# oresat-batteries-prototype.net
KiCad netlist of a schematic drawn in EAGLE
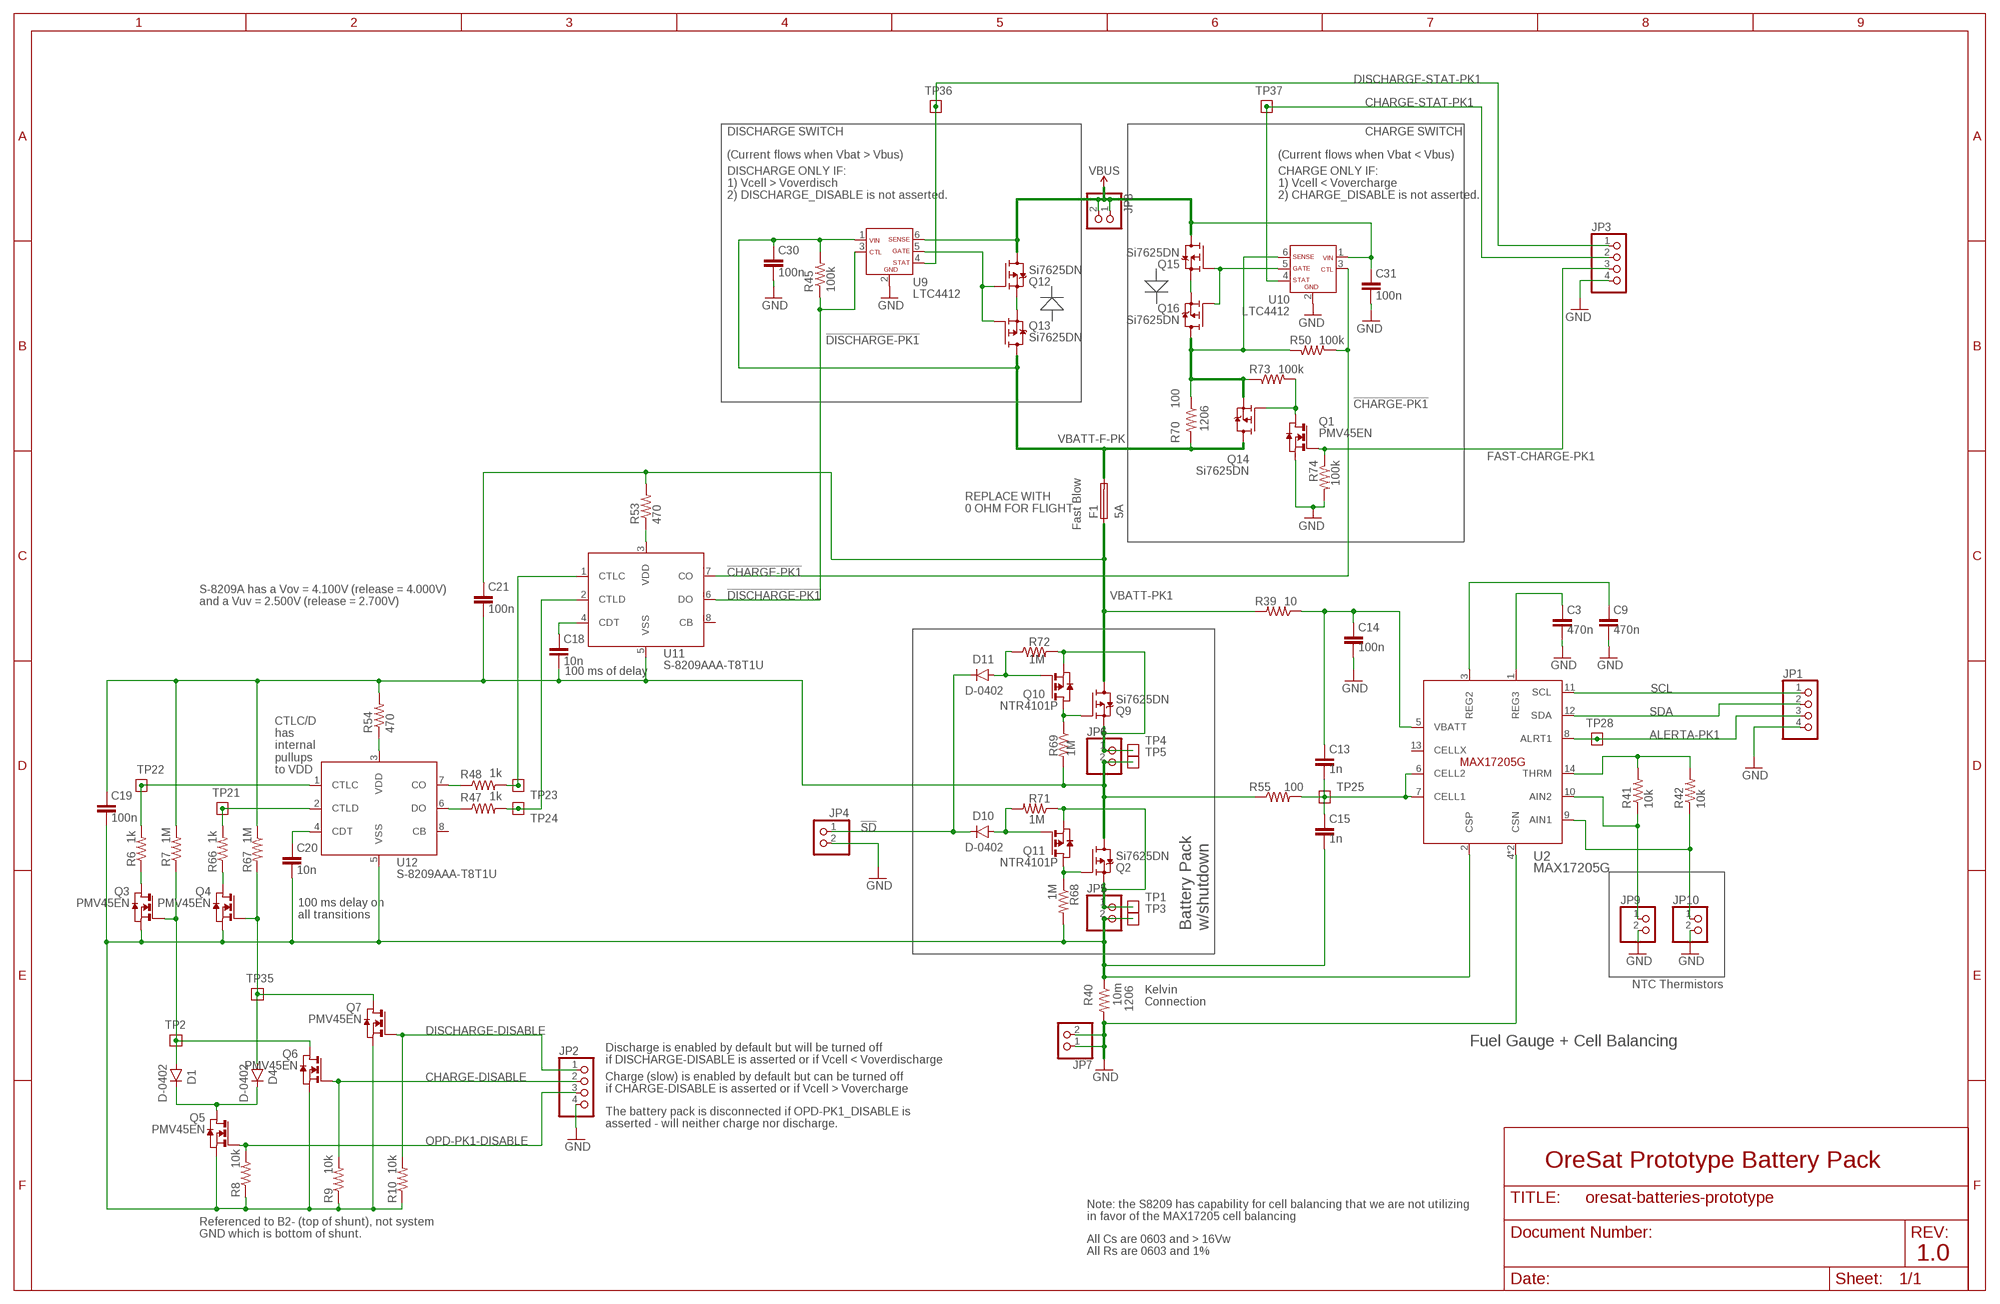
[diagram p0: schematic, sheet 1]

(export (version "E")
  (design (tool "Eeschema 10.0.6"))
  (components
    (comp (ref "C3")
      (value "470n")
      (footprint "eagle-import:.0603-C-NOSILK")
      (libsource (lib "eagle-import") (part "C-EU0603-C-NOSILK"))
    )
    (comp (ref "C9")
      (value "470n")
      (footprint "eagle-import:.0603-C-NOSILK")
      (libsource (lib "eagle-import") (part "C-EU0603-C-NOSILK"))
    )
    (comp (ref "C13")
      (value "1n")
      (footprint "eagle-import:.0603-C-NOSILK")
      (libsource (lib "eagle-import") (part "C-EU0603-C-NOSILK"))
    )
    (comp (ref "C14")
      (value "100n")
      (footprint "eagle-import:.0603-C-NOSILK")
      (libsource (lib "eagle-import") (part "C-EU0603-C-NOSILK"))
    )
    (comp (ref "C15")
      (value "1n")
      (footprint "eagle-import:.0603-C-NOSILK")
      (libsource (lib "eagle-import") (part "C-EU0603-C-NOSILK"))
    )
    (comp (ref "C18")
      (value "10n")
      (footprint "eagle-import:.0603-C-NOSILK")
      (libsource (lib "eagle-import") (part "C-EU0603-C-NOSILK"))
    )
    (comp (ref "C19")
      (value "100n")
      (footprint "eagle-import:.0603-C-NOSILK")
      (libsource (lib "eagle-import") (part "C-EU0603-C-NOSILK"))
    )
    (comp (ref "C20")
      (value "10n")
      (footprint "eagle-import:.0603-C-NOSILK")
      (libsource (lib "eagle-import") (part "C-EU0603-C-NOSILK"))
    )
    (comp (ref "C21")
      (value "100n")
      (footprint "eagle-import:.0603-C-NOSILK")
      (libsource (lib "eagle-import") (part "C-EU0603-C-NOSILK"))
    )
    (comp (ref "C30")
      (value "100n")
      (footprint "eagle-import:.0603-C-NOSILK")
      (libsource (lib "eagle-import") (part "C-EU0603-C-NOSILK"))
    )
    (comp (ref "C31")
      (value "100n")
      (footprint "eagle-import:.0603-C-NOSILK")
      (libsource (lib "eagle-import") (part "C-EU0603-C-NOSILK"))
    )
    (comp (ref "D1")
      (value "D-0402")
      (footprint "eagle-import:.0402-B-NOSILK-DIODE")
      (fields (field (name "MFR") "Micro Commercial Co") (field (name "MPN") "1N4148WL2-TP"))
      (libsource (lib "eagle-import") (part "D-0402"))
    )
    (comp (ref "D4")
      (value "D-0402")
      (footprint "eagle-import:.0402-B-NOSILK-DIODE")
      (fields (field (name "MFR") "Micro Commercial Co") (field (name "MPN") "1N4148WL2-TP"))
      (libsource (lib "eagle-import") (part "D-0402"))
    )
    (comp (ref "D10")
      (value "D-0402")
      (footprint "eagle-import:.0402-B-NOSILK-DIODE")
      (fields (field (name "MFR") "Micro Commercial Co") (field (name "MPN") "1N4148WL2-TP"))
      (libsource (lib "eagle-import") (part "D-0402"))
    )
    (comp (ref "D11")
      (value "D-0402")
      (footprint "eagle-import:.0402-B-NOSILK-DIODE")
      (fields (field (name "MFR") "Micro Commercial Co") (field (name "MPN") "1N4148WL2-TP"))
      (libsource (lib "eagle-import") (part "D-0402"))
    )
    (comp (ref "F1")
      (value "5A")
      (footprint "eagle-import:C0603")
      (fields (field (name "MFR") "Panasonic") (field (name "MPN") "ERB-RE5R00V"))
      (libsource (lib "eagle-import") (part "F-ERB_RE5R00V-FUSE"))
    )
    (comp (ref "JP1")
      (value "PINHD-1X4")
      (footprint "eagle-import:1X04")
      (libsource (lib "eagle-import") (part "PINHD-1X4"))
    )
    (comp (ref "JP2")
      (value "PINHD-1X4")
      (footprint "eagle-import:1X04")
      (libsource (lib "eagle-import") (part "PINHD-1X4"))
    )
    (comp (ref "JP3")
      (value "PINHD-1X4")
      (footprint "eagle-import:1X04")
      (libsource (lib "eagle-import") (part "PINHD-1X4"))
    )
    (comp (ref "JP4")
      (value "PINHD-1X2")
      (footprint "eagle-import:1X02")
      (libsource (lib "eagle-import") (part "PINHD-1X2"))
    )
    (comp (ref "JP5")
      (value "PINHD-1X2")
      (footprint "eagle-import:1X02")
      (libsource (lib "eagle-import") (part "PINHD-1X2"))
    )
    (comp (ref "JP6")
      (value "PINHD-1X2")
      (footprint "eagle-import:1X02")
      (libsource (lib "eagle-import") (part "PINHD-1X2"))
    )
    (comp (ref "JP7")
      (value "PINHD-1X2")
      (footprint "eagle-import:1X02")
      (libsource (lib "eagle-import") (part "PINHD-1X2"))
    )
    (comp (ref "JP8")
      (value "PINHD-1X2")
      (footprint "eagle-import:1X02")
      (libsource (lib "eagle-import") (part "PINHD-1X2"))
    )
    (comp (ref "JP9")
      (value "PINHD-1X2")
      (footprint "eagle-import:1X02")
      (libsource (lib "eagle-import") (part "PINHD-1X2"))
    )
    (comp (ref "JP10")
      (value "PINHD-1X2")
      (footprint "eagle-import:1X02")
      (libsource (lib "eagle-import") (part "PINHD-1X2"))
    )
    (comp (ref "Q1")
      (value "PMV45EN")
      (footprint "eagle-import:SOT23")
      (fields (field (name "MFR") "Diodes Inc") (field (name "MPN") "DMG2302UK-7"))
      (libsource (lib "eagle-import") (part "PMV45EN"))
    )
    (comp (ref "Q2")
      (value "Si7625DN")
      (footprint "eagle-import:POWERPAK-1212-8")
      (fields (field (name "MFR") "Vishay Siliconix") (field (name "MPN") "SI7625DN-T1-GE3"))
      (libsource (lib "eagle-import") (part "Q-VISHAY-MOSFET-PCH-POWERPAK-1212-8"))
    )
    (comp (ref "Q3")
      (value "PMV45EN")
      (footprint "eagle-import:SOT23")
      (fields (field (name "MFR") "Diodes Inc") (field (name "MPN") "DMG2302UK-7"))
      (libsource (lib "eagle-import") (part "PMV45EN"))
    )
    (comp (ref "Q4")
      (value "PMV45EN")
      (footprint "eagle-import:SOT23")
      (fields (field (name "MFR") "Diodes Inc") (field (name "MPN") "DMG2302UK-7"))
      (libsource (lib "eagle-import") (part "PMV45EN"))
    )
    (comp (ref "Q5")
      (value "PMV45EN")
      (footprint "eagle-import:SOT23")
      (fields (field (name "MFR") "Diodes Inc") (field (name "MPN") "DMG2302UK-7"))
      (libsource (lib "eagle-import") (part "PMV45EN"))
    )
    (comp (ref "Q6")
      (value "PMV45EN")
      (footprint "eagle-import:SOT23")
      (fields (field (name "MFR") "Diodes Inc") (field (name "MPN") "DMG2302UK-7"))
      (libsource (lib "eagle-import") (part "PMV45EN"))
    )
    (comp (ref "Q7")
      (value "PMV45EN")
      (footprint "eagle-import:SOT23")
      (fields (field (name "MFR") "Diodes Inc") (field (name "MPN") "DMG2302UK-7"))
      (libsource (lib "eagle-import") (part "PMV45EN"))
    )
    (comp (ref "Q9")
      (value "Si7625DN")
      (footprint "eagle-import:POWERPAK-1212-8")
      (fields (field (name "MFR") "Vishay Siliconix") (field (name "MPN") "SI7625DN-T1-GE3"))
      (libsource (lib "eagle-import") (part "Q-VISHAY-MOSFET-PCH-POWERPAK-1212-8"))
    )
    (comp (ref "Q10")
      (value "NTR4101P")
      (footprint "eagle-import:SOT23")
      (fields (field (name "MFR") "Diodes Inc") (field (name "MPN") "DMG3401LSN-7"))
      (libsource (lib "eagle-import") (part "NTR4101P"))
    )
    (comp (ref "Q11")
      (value "NTR4101P")
      (footprint "eagle-import:SOT23")
      (fields (field (name "MFR") "Diodes Inc") (field (name "MPN") "DMG3401LSN-7"))
      (libsource (lib "eagle-import") (part "NTR4101P"))
    )
    (comp (ref "Q12")
      (value "Si7625DN")
      (footprint "eagle-import:POWERPAK-1212-8")
      (fields (field (name "MFR") "Vishay Siliconix") (field (name "MPN") "SI7625DN-T1-GE3"))
      (libsource (lib "eagle-import") (part "Q-VISHAY-MOSFET-PCH-POWERPAK-1212-8"))
    )
    (comp (ref "Q13")
      (value "Si7625DN")
      (footprint "eagle-import:POWERPAK-1212-8")
      (fields (field (name "MFR") "Vishay Siliconix") (field (name "MPN") "SI7625DN-T1-GE3"))
      (libsource (lib "eagle-import") (part "Q-VISHAY-MOSFET-PCH-POWERPAK-1212-8"))
    )
    (comp (ref "Q14")
      (value "Si7625DN")
      (footprint "eagle-import:POWERPAK-1212-8")
      (fields (field (name "MFR") "Vishay Siliconix") (field (name "MPN") "SI7625DN-T1-GE3"))
      (libsource (lib "eagle-import") (part "Q-VISHAY-MOSFET-PCH-POWERPAK-1212-8"))
    )
    (comp (ref "Q15")
      (value "Si7625DN")
      (footprint "eagle-import:POWERPAK-1212-8")
      (fields (field (name "MFR") "Vishay Siliconix") (field (name "MPN") "SI7625DN-T1-GE3"))
      (libsource (lib "eagle-import") (part "Q-VISHAY-MOSFET-PCH-POWERPAK-1212-8"))
    )
    (comp (ref "Q16")
      (value "Si7625DN")
      (footprint "eagle-import:POWERPAK-1212-8")
      (fields (field (name "MFR") "Vishay Siliconix") (field (name "MPN") "SI7625DN-T1-GE3"))
      (libsource (lib "eagle-import") (part "Q-VISHAY-MOSFET-PCH-POWERPAK-1212-8"))
    )
    (comp (ref "R6")
      (value "1k")
      (footprint "eagle-import:.0603-C-NOSILK")
      (libsource (lib "eagle-import") (part "R-US_0603-C-NOSILK"))
    )
    (comp (ref "R7")
      (value "1M")
      (footprint "eagle-import:.0603-C-NOSILK")
      (libsource (lib "eagle-import") (part "R-US_0603-C-NOSILK"))
    )
    (comp (ref "R8")
      (value "10k")
      (footprint "eagle-import:.0603-C-NOSILK")
      (libsource (lib "eagle-import") (part "R-US_0603-C-NOSILK"))
    )
    (comp (ref "R9")
      (value "10k")
      (footprint "eagle-import:.0603-C-NOSILK")
      (libsource (lib "eagle-import") (part "R-US_0603-C-NOSILK"))
    )
    (comp (ref "R10")
      (value "10k")
      (footprint "eagle-import:.0603-C-NOSILK")
      (libsource (lib "eagle-import") (part "R-US_0603-C-NOSILK"))
    )
    (comp (ref "R39")
      (value "10")
      (footprint "eagle-import:.0603-C-NOSILK")
      (libsource (lib "eagle-import") (part "R-US_0603-C-NOSILK"))
    )
    (comp (ref "R40")
      (value "10m")
      (footprint "eagle-import:1206-C")
      (libsource (lib "eagle-import") (part "R-US_1206-C"))
    )
    (comp (ref "R41")
      (value "10k")
      (footprint "eagle-import:.0603-C-NOSILK")
      (libsource (lib "eagle-import") (part "R-US_0603-C-NOSILK"))
    )
    (comp (ref "R42")
      (value "10k")
      (footprint "eagle-import:.0603-C-NOSILK")
      (libsource (lib "eagle-import") (part "R-US_0603-C-NOSILK"))
    )
    (comp (ref "R45")
      (value "100k")
      (footprint "eagle-import:.0603-C-NOSILK")
      (libsource (lib "eagle-import") (part "R-US_0603-C-NOSILK"))
    )
    (comp (ref "R47")
      (value "1k")
      (footprint "eagle-import:.0603-C-NOSILK")
      (libsource (lib "eagle-import") (part "R-US_0603-C-NOSILK"))
    )
    (comp (ref "R48")
      (value "1k")
      (footprint "eagle-import:.0603-C-NOSILK")
      (libsource (lib "eagle-import") (part "R-US_0603-C-NOSILK"))
    )
    (comp (ref "R50")
      (value "100k")
      (footprint "eagle-import:.0603-C-NOSILK")
      (libsource (lib "eagle-import") (part "R-US_0603-C-NOSILK"))
    )
    (comp (ref "R53")
      (value "470")
      (footprint "eagle-import:.0603-C-NOSILK")
      (libsource (lib "eagle-import") (part "R-US_0603-C-NOSILK"))
    )
    (comp (ref "R54")
      (value "470")
      (footprint "eagle-import:.0603-C-NOSILK")
      (libsource (lib "eagle-import") (part "R-US_0603-C-NOSILK"))
    )
    (comp (ref "R55")
      (value "100")
      (footprint "eagle-import:.0603-C-NOSILK")
      (libsource (lib "eagle-import") (part "R-US_0603-C-NOSILK"))
    )
    (comp (ref "R66")
      (value "1k")
      (footprint "eagle-import:.0603-C-NOSILK")
      (libsource (lib "eagle-import") (part "R-US_0603-C-NOSILK"))
    )
    (comp (ref "R67")
      (value "1M")
      (footprint "eagle-import:.0603-C-NOSILK")
      (libsource (lib "eagle-import") (part "R-US_0603-C-NOSILK"))
    )
    (comp (ref "R68")
      (value "1M")
      (footprint "eagle-import:.0603-C-NOSILK")
      (libsource (lib "eagle-import") (part "R-US_0603-C-NOSILK"))
    )
    (comp (ref "R69")
      (value "1M")
      (footprint "eagle-import:.0603-C-NOSILK")
      (libsource (lib "eagle-import") (part "R-US_0603-C-NOSILK"))
    )
    (comp (ref "R70")
      (value "100")
      (footprint "eagle-import:1206-C")
      (libsource (lib "eagle-import") (part "R-US_1206-C"))
    )
    (comp (ref "R71")
      (value "1M")
      (footprint "eagle-import:.0603-C-NOSILK")
      (libsource (lib "eagle-import") (part "R-US_0603-C-NOSILK"))
    )
    (comp (ref "R72")
      (value "1M")
      (footprint "eagle-import:.0603-C-NOSILK")
      (libsource (lib "eagle-import") (part "R-US_0603-C-NOSILK"))
    )
    (comp (ref "R73")
      (value "100k")
      (footprint "eagle-import:.0603-C-NOSILK")
      (libsource (lib "eagle-import") (part "R-US_0603-C-NOSILK"))
    )
    (comp (ref "R74")
      (value "100k")
      (footprint "eagle-import:.0603-C-NOSILK")
      (libsource (lib "eagle-import") (part "R-US_0603-C-NOSILK"))
    )
    (comp (ref "TP1")
      (value "TEST-POINT")
      (footprint "eagle-import:2MM-TEST-POINT")
      (libsource (lib "eagle-import") (part "TEST-POINT"))
    )
    (comp (ref "TP2")
      (value "TEST-POINT")
      (footprint "eagle-import:2MM-TEST-POINT")
      (libsource (lib "eagle-import") (part "TEST-POINT"))
    )
    (comp (ref "TP3")
      (value "TEST-POINT")
      (footprint "eagle-import:2MM-TEST-POINT")
      (libsource (lib "eagle-import") (part "TEST-POINT"))
    )
    (comp (ref "TP4")
      (value "TEST-POINT")
      (footprint "eagle-import:2MM-TEST-POINT")
      (libsource (lib "eagle-import") (part "TEST-POINT"))
    )
    (comp (ref "TP5")
      (value "TEST-POINT")
      (footprint "eagle-import:2MM-TEST-POINT")
      (libsource (lib "eagle-import") (part "TEST-POINT"))
    )
    (comp (ref "TP21")
      (value "TEST-POINT")
      (footprint "eagle-import:2MM-TEST-POINT")
      (libsource (lib "eagle-import") (part "TEST-POINT"))
    )
    (comp (ref "TP22")
      (value "TEST-POINT")
      (footprint "eagle-import:2MM-TEST-POINT")
      (libsource (lib "eagle-import") (part "TEST-POINT"))
    )
    (comp (ref "TP23")
      (value "TEST-POINT")
      (footprint "eagle-import:2MM-TEST-POINT")
      (libsource (lib "eagle-import") (part "TEST-POINT"))
    )
    (comp (ref "TP24")
      (value "TEST-POINT")
      (footprint "eagle-import:2MM-TEST-POINT")
      (libsource (lib "eagle-import") (part "TEST-POINT"))
    )
    (comp (ref "TP25")
      (value "TEST-POINT")
      (footprint "eagle-import:2MM-TEST-POINT")
      (libsource (lib "eagle-import") (part "TEST-POINT"))
    )
    (comp (ref "TP28")
      (value "TEST-POINT")
      (footprint "eagle-import:2MM-TEST-POINT")
      (libsource (lib "eagle-import") (part "TEST-POINT"))
    )
    (comp (ref "TP35")
      (value "TEST-POINT")
      (footprint "eagle-import:2MM-TEST-POINT")
      (libsource (lib "eagle-import") (part "TEST-POINT"))
    )
    (comp (ref "TP36")
      (value "TEST-POINT")
      (footprint "eagle-import:2MM-TEST-POINT")
      (libsource (lib "eagle-import") (part "TEST-POINT"))
    )
    (comp (ref "TP37")
      (value "TEST-POINT")
      (footprint "eagle-import:2MM-TEST-POINT")
      (libsource (lib "eagle-import") (part "TEST-POINT"))
    )
    (comp (ref "U2")
      (value "MAX17205G")
      (footprint "eagle-import:21-0137I_T1433-2")
      (fields (field (name "MFR") "Maxim Integrated") (field (name "MPN") "MAX17205G+T"))
      (libsource (lib "eagle-import") (part "MAX17205G"))
    )
    (comp (ref "U9")
      (value "LTC4412")
      (footprint "eagle-import:SOT23-6")
      (fields (field (name "MFR") "Linear Technology") (field (name "MPN") "LTC4412HS6#TRMPBF"))
      (libsource (lib "eagle-import") (part "LTC4412"))
    )
    (comp (ref "U10")
      (value "LTC4412")
      (footprint "eagle-import:SOT23-6")
      (fields (field (name "MFR") "Linear Technology") (field (name "MPN") "LTC4412HS6#TRMPBF"))
      (libsource (lib "eagle-import") (part "LTC4412"))
    )
    (comp (ref "U11")
      (value "S-8209AAA-T8T1U")
      (footprint "eagle-import:TSSOP8")
      (fields (field (name "MFR") "Ablic"))
      (libsource (lib "eagle-import") (part "S-8209AXXT"))
    )
    (comp (ref "U12")
      (value "S-8209AAA-T8T1U")
      (footprint "eagle-import:TSSOP8")
      (fields (field (name "MFR") "Ablic"))
      (libsource (lib "eagle-import") (part "S-8209AXXT"))
    )
  )
  (nets
    (net (code "1") (name "/ALERTA-PK1") (class "Default")
      (node (ref "JP1") (pin "3") (pinfunction "3_3") (pintype "passive"))
      (node (ref "TP28") (pin "1") (pinfunction "1_1") (pintype "passive"))
      (node (ref "U2") (pin "8") (pinfunction "ALRT1_8") (pintype "output"))
    )
    (net (code "2") (name "/CHARGE-DISABLE") (class "Default")
      (node (ref "JP2") (pin "2") (pinfunction "2_2") (pintype "passive"))
      (node (ref "Q6") (pin "1") (pinfunction "G_1") (pintype "passive"))
      (node (ref "R9") (pin "2") (pinfunction "2_2") (pintype "passive"))
    )
    (net (code "3") (name "/CHARGE-STAT-PK1") (class "Default")
      (node (ref "JP3") (pin "2") (pinfunction "2_2") (pintype "passive"))
      (node (ref "TP37") (pin "1") (pinfunction "1_1") (pintype "passive"))
      (node (ref "U10") (pin "4") (pinfunction "STAT_4") (pintype "open_collector"))
    )
    (net (code "4") (name "/DISCHARGE-DISABLE") (class "Default")
      (node (ref "JP2") (pin "1") (pinfunction "1_1") (pintype "passive"))
      (node (ref "Q7") (pin "1") (pinfunction "G_1") (pintype "passive"))
      (node (ref "R10") (pin "2") (pinfunction "2_2") (pintype "passive"))
    )
    (net (code "5") (name "/DISCHARGE-STAT-PK1") (class "Default")
      (node (ref "JP3") (pin "1") (pinfunction "1_1") (pintype "passive"))
      (node (ref "TP36") (pin "1") (pinfunction "1_1") (pintype "passive"))
      (node (ref "U9") (pin "4") (pinfunction "STAT_4") (pintype "open_collector"))
    )
    (net (code "6") (name "/FAST-CHARGE-PK1") (class "Default")
      (node (ref "JP3") (pin "3") (pinfunction "3_3") (pintype "passive"))
      (node (ref "Q1") (pin "1") (pinfunction "G_1") (pintype "passive"))
      (node (ref "R74") (pin "1") (pinfunction "1_1") (pintype "passive"))
    )
    (net (code "7") (name "/OPD-PK1-DISABLE") (class "Default")
      (node (ref "JP2") (pin "3") (pinfunction "3_3") (pintype "passive"))
      (node (ref "Q5") (pin "1") (pinfunction "G_1") (pintype "passive"))
      (node (ref "R8") (pin "2") (pinfunction "2_2") (pintype "passive"))
    )
    (net (code "8") (name "/SCL") (class "Default")
      (node (ref "JP1") (pin "1") (pinfunction "1_1") (pintype "passive"))
      (node (ref "U2") (pin "11") (pinfunction "SCL_11") (pintype "input"))
    )
    (net (code "9") (name "/SDA") (class "Default")
      (node (ref "JP1") (pin "2") (pinfunction "2_2") (pintype "passive"))
      (node (ref "U2") (pin "12") (pinfunction "SDA_12") (pintype "bidirectional"))
    )
    (net (code "10") (name "/VBATT-F-PK") (class "Default")
      (node (ref "C30") (pin "1") (pinfunction "1_1") (pintype "passive"))
      (node (ref "F1") (pin "2") (pinfunction "2_2") (pintype "passive"))
      (node (ref "Q13") (pin "5") (pinfunction "D_5") (pintype "passive"))
      (node (ref "Q13") (pin "6") (pinfunction "D_6") (pintype "passive"))
      (node (ref "Q13") (pin "7") (pinfunction "D_7") (pintype "passive"))
      (node (ref "Q13") (pin "8") (pinfunction "D_8") (pintype "passive"))
      (node (ref "Q13") (pin "PAD") (pinfunction "D_PAD") (pintype "passive"))
      (node (ref "Q14") (pin "5") (pinfunction "D_5") (pintype "passive"))
      (node (ref "Q14") (pin "6") (pinfunction "D_6") (pintype "passive"))
      (node (ref "Q14") (pin "7") (pinfunction "D_7") (pintype "passive"))
      (node (ref "Q14") (pin "8") (pinfunction "D_8") (pintype "passive"))
      (node (ref "Q14") (pin "PAD") (pinfunction "D_PAD") (pintype "passive"))
      (node (ref "R45") (pin "2") (pinfunction "2_2") (pintype "passive"))
      (node (ref "R70") (pin "2") (pinfunction "2_2") (pintype "passive"))
      (node (ref "U9") (pin "1") (pinfunction "VIN_1") (pintype "power_in"))
    )
    (net (code "11") (name "/VBATT-PK1") (class "Default")
      (node (ref "C21") (pin "1") (pinfunction "1_1") (pintype "passive"))
      (node (ref "F1") (pin "1") (pinfunction "1_1") (pintype "passive"))
      (node (ref "Q9") (pin "5") (pinfunction "D_5") (pintype "passive"))
      (node (ref "Q9") (pin "6") (pinfunction "D_6") (pintype "passive"))
      (node (ref "Q9") (pin "7") (pinfunction "D_7") (pintype "passive"))
      (node (ref "Q9") (pin "8") (pinfunction "D_8") (pintype "passive"))
      (node (ref "Q9") (pin "PAD") (pinfunction "D_PAD") (pintype "passive"))
      (node (ref "R39") (pin "2") (pinfunction "2_2") (pintype "passive"))
      (node (ref "R53") (pin "2") (pinfunction "2_2") (pintype "passive"))
    )
    (net (code "12") (name "/~{CHARGE-PK1}") (class "Default")
      (node (ref "R50") (pin "1") (pinfunction "1_1") (pintype "passive"))
      (node (ref "U10") (pin "3") (pinfunction "CTL_3") (pintype "input"))
      (node (ref "U11") (pin "7") (pinfunction "CO_7") (pintype "open_collector"))
    )
    (net (code "13") (name "/~{DISCHARGE-PK1}") (class "Default")
      (node (ref "R45") (pin "1") (pinfunction "1_1") (pintype "passive"))
      (node (ref "U11") (pin "6") (pinfunction "DO_6") (pintype "open_collector"))
      (node (ref "U9") (pin "3") (pinfunction "CTL_3") (pintype "input"))
    )
    (net (code "14") (name "/~{SD}") (class "Default")
      (node (ref "D10") (pin "C") (pinfunction "C_C") (pintype "passive"))
      (node (ref "D11") (pin "C") (pinfunction "C_C") (pintype "passive"))
      (node (ref "JP4") (pin "1") (pinfunction "1_1") (pintype "passive"))
    )
    (net (code "15") (name "GND") (class "Default")
      (node (ref "C14") (pin "2") (pinfunction "2_2") (pintype "passive"))
      (node (ref "C3") (pin "2") (pinfunction "2_2") (pintype "passive"))
      (node (ref "C30") (pin "2") (pinfunction "2_2") (pintype "passive"))
      (node (ref "C31") (pin "2") (pinfunction "2_2") (pintype "passive"))
      (node (ref "C9") (pin "2") (pinfunction "2_2") (pintype "passive"))
      (node (ref "JP1") (pin "4") (pinfunction "4_4") (pintype "passive"))
      (node (ref "JP10") (pin "2") (pinfunction "2_2") (pintype "passive"))
      (node (ref "JP2") (pin "4") (pinfunction "4_4") (pintype "passive"))
      (node (ref "JP3") (pin "4") (pinfunction "4_4") (pintype "passive"))
      (node (ref "JP4") (pin "2") (pinfunction "2_2") (pintype "passive"))
      (node (ref "JP7") (pin "1") (pinfunction "1_1") (pintype "passive"))
      (node (ref "JP7") (pin "2") (pinfunction "2_2") (pintype "passive"))
      (node (ref "JP9") (pin "2") (pinfunction "2_2") (pintype "passive"))
      (node (ref "Q1") (pin "2") (pinfunction "S_2") (pintype "passive"))
      (node (ref "R40") (pin "2") (pinfunction "2_2") (pintype "passive"))
      (node (ref "R74") (pin "2") (pinfunction "2_2") (pintype "passive"))
      (node (ref "U10") (pin "2") (pinfunction "GND_2") (pintype "power_in"))
      (node (ref "U2") (pin "4") (pinfunction "CSN_4") (pintype "passive"))
      (node (ref "U2") (pin "EP") (pinfunction "CSN_EP") (pintype "passive"))
      (node (ref "U9") (pin "2") (pinfunction "GND_2") (pintype "power_in"))
    )
    (net (code "16") (name "Net-(Q1-D)") (class "Default")
      (node (ref "Q1") (pin "3") (pinfunction "D_3") (pintype "passive"))
      (node (ref "Q14") (pin "4") (pinfunction "G_4") (pintype "passive"))
      (node (ref "R73") (pin "2") (pinfunction "2_2") (pintype "passive"))
    )
    (net (code "17") (name "Net-(Q3-D)") (class "Default")
      (node (ref "Q3") (pin "3") (pinfunction "D_3") (pintype "passive"))
      (node (ref "R6") (pin "1") (pinfunction "1_1") (pintype "passive"))
    )
    (net (code "18") (name "Net-(Q3-G)") (class "Default")
      (node (ref "D1") (pin "A") (pinfunction "A_A") (pintype "passive"))
      (node (ref "Q3") (pin "1") (pinfunction "G_1") (pintype "passive"))
      (node (ref "Q6") (pin "3") (pinfunction "D_3") (pintype "passive"))
      (node (ref "R7") (pin "1") (pinfunction "1_1") (pintype "passive"))
      (node (ref "TP2") (pin "1") (pinfunction "1_1") (pintype "passive"))
    )
    (net (code "19") (name "Net-(Q3-S)") (class "Default")
      (node (ref "C15") (pin "2") (pinfunction "2_2") (pintype "passive"))
      (node (ref "C19") (pin "2") (pinfunction "2_2") (pintype "passive"))
      (node (ref "C20") (pin "2") (pinfunction "2_2") (pintype "passive"))
      (node (ref "JP5") (pin "2") (pinfunction "2_2") (pintype "passive"))
      (node (ref "Q3") (pin "2") (pinfunction "S_2") (pintype "passive"))
      (node (ref "Q4") (pin "2") (pinfunction "S_2") (pintype "passive"))
      (node (ref "Q5") (pin "2") (pinfunction "S_2") (pintype "passive"))
      (node (ref "Q6") (pin "2") (pinfunction "S_2") (pintype "passive"))
      (node (ref "Q7") (pin "2") (pinfunction "S_2") (pintype "passive"))
      (node (ref "R10") (pin "1") (pinfunction "1_1") (pintype "passive"))
      (node (ref "R40") (pin "1") (pinfunction "1_1") (pintype "passive"))
      (node (ref "R68") (pin "2") (pinfunction "2_2") (pintype "passive"))
      (node (ref "R8") (pin "1") (pinfunction "1_1") (pintype "passive"))
      (node (ref "R9") (pin "1") (pinfunction "1_1") (pintype "passive"))
      (node (ref "TP3") (pin "1") (pinfunction "1_1") (pintype "passive"))
      (node (ref "U12") (pin "5") (pinfunction "VSS_5") (pintype "power_in"))
      (node (ref "U2") (pin "2") (pinfunction "CSP_2") (pintype "passive"))
    )
    (net (code "20") (name "Net-(Q4-D)") (class "Default")
      (node (ref "Q4") (pin "3") (pinfunction "D_3") (pintype "passive"))
      (node (ref "R66") (pin "1") (pinfunction "1_1") (pintype "passive"))
    )
    (net (code "21") (name "Net-(Q4-G)") (class "Default")
      (node (ref "D4") (pin "A") (pinfunction "A_A") (pintype "passive"))
      (node (ref "Q4") (pin "1") (pinfunction "G_1") (pintype "passive"))
      (node (ref "Q7") (pin "3") (pinfunction "D_3") (pintype "passive"))
      (node (ref "R67") (pin "2") (pinfunction "2_2") (pintype "passive"))
      (node (ref "TP35") (pin "1") (pinfunction "1_1") (pintype "passive"))
    )
    (net (code "22") (name "Net-(Q5-D)") (class "Default")
      (node (ref "D1") (pin "C") (pinfunction "C_C") (pintype "passive"))
      (node (ref "D4") (pin "C") (pinfunction "C_C") (pintype "passive"))
      (node (ref "Q5") (pin "3") (pinfunction "D_3") (pintype "passive"))
    )
    (net (code "23") (name "Net-(Q10-D)") (class "Default")
      (node (ref "Q10") (pin "3") (pinfunction "D_3") (pintype "passive"))
      (node (ref "Q9") (pin "4") (pinfunction "G_4") (pintype "passive"))
      (node (ref "R69") (pin "1") (pinfunction "1_1") (pintype "passive"))
    )
    (net (code "24") (name "Net-(Q10-G)") (class "Default")
      (node (ref "D11") (pin "A") (pinfunction "A_A") (pintype "passive"))
      (node (ref "Q10") (pin "1") (pinfunction "G_1") (pintype "passive"))
      (node (ref "R72") (pin "1") (pinfunction "1_1") (pintype "passive"))
    )
    (net (code "25") (name "Net-(Q10-S)") (class "Default")
      (node (ref "JP6") (pin "1") (pinfunction "1_1") (pintype "passive"))
      (node (ref "Q10") (pin "2") (pinfunction "S_2") (pintype "passive"))
      (node (ref "Q9") (pin "1") (pinfunction "S_1") (pintype "passive"))
      (node (ref "Q9") (pin "2") (pinfunction "S_2") (pintype "passive"))
      (node (ref "Q9") (pin "3") (pinfunction "S_3") (pintype "passive"))
      (node (ref "R72") (pin "2") (pinfunction "2_2") (pintype "passive"))
      (node (ref "TP4") (pin "1") (pinfunction "1_1") (pintype "passive"))
    )
    (net (code "26") (name "Net-(Q11-D)") (class "Default")
      (node (ref "Q11") (pin "3") (pinfunction "D_3") (pintype "passive"))
      (node (ref "Q2") (pin "4") (pinfunction "G_4") (pintype "passive"))
      (node (ref "R68") (pin "1") (pinfunction "1_1") (pintype "passive"))
    )
    (net (code "27") (name "Net-(Q11-G)") (class "Default")
      (node (ref "D10") (pin "A") (pinfunction "A_A") (pintype "passive"))
      (node (ref "Q11") (pin "1") (pinfunction "G_1") (pintype "passive"))
      (node (ref "R71") (pin "2") (pinfunction "2_2") (pintype "passive"))
    )
    (net (code "28") (name "Net-(Q11-S)") (class "Default")
      (node (ref "JP5") (pin "1") (pinfunction "1_1") (pintype "passive"))
      (node (ref "Q11") (pin "2") (pinfunction "S_2") (pintype "passive"))
      (node (ref "Q2") (pin "1") (pinfunction "S_1") (pintype "passive"))
      (node (ref "Q2") (pin "2") (pinfunction "S_2") (pintype "passive"))
      (node (ref "Q2") (pin "3") (pinfunction "S_3") (pintype "passive"))
      (node (ref "R71") (pin "1") (pinfunction "1_1") (pintype "passive"))
      (node (ref "TP1") (pin "1") (pinfunction "1_1") (pintype "passive"))
    )
    (net (code "29") (name "Net-(Q12-G)") (class "Default")
      (node (ref "Q12") (pin "4") (pinfunction "G_4") (pintype "passive"))
      (node (ref "Q13") (pin "4") (pinfunction "G_4") (pintype "passive"))
      (node (ref "U9") (pin "5") (pinfunction "GATE_5") (pintype "output"))
    )
    (net (code "30") (name "Net-(Q12-S-Pad1)") (class "Default")
      (node (ref "Q12") (pin "1") (pinfunction "S_1") (pintype "passive"))
      (node (ref "Q12") (pin "2") (pinfunction "S_2") (pintype "passive"))
      (node (ref "Q12") (pin "3") (pinfunction "S_3") (pintype "passive"))
      (node (ref "Q13") (pin "1") (pinfunction "S_1") (pintype "passive"))
      (node (ref "Q13") (pin "2") (pinfunction "S_2") (pintype "passive"))
      (node (ref "Q13") (pin "3") (pinfunction "S_3") (pintype "passive"))
    )
    (net (code "31") (name "Net-(Q15-G)") (class "Default")
      (node (ref "Q15") (pin "4") (pinfunction "G_4") (pintype "passive"))
      (node (ref "Q16") (pin "4") (pinfunction "G_4") (pintype "passive"))
      (node (ref "U10") (pin "5") (pinfunction "GATE_5") (pintype "output"))
    )
    (net (code "32") (name "Net-(Q15-S-Pad1)") (class "Default")
      (node (ref "Q15") (pin "1") (pinfunction "S_1") (pintype "passive"))
      (node (ref "Q15") (pin "2") (pinfunction "S_2") (pintype "passive"))
      (node (ref "Q15") (pin "3") (pinfunction "S_3") (pintype "passive"))
      (node (ref "Q16") (pin "1") (pinfunction "S_1") (pintype "passive"))
      (node (ref "Q16") (pin "2") (pinfunction "S_2") (pintype "passive"))
      (node (ref "Q16") (pin "3") (pinfunction "S_3") (pintype "passive"))
    )
    (net (code "33") (name "Net-(U2-AIN1)") (class "Default")
      (node (ref "JP10") (pin "1") (pinfunction "1_1") (pintype "passive"))
      (node (ref "R42") (pin "1") (pinfunction "1_1") (pintype "passive"))
      (node (ref "U2") (pin "9") (pinfunction "AIN1_9") (pintype "input"))
    )
    (net (code "34") (name "Net-(U2-AIN2)") (class "Default")
      (node (ref "JP9") (pin "1") (pinfunction "1_1") (pintype "passive"))
      (node (ref "R41") (pin "1") (pinfunction "1_1") (pintype "passive"))
      (node (ref "U2") (pin "10") (pinfunction "AIN2_10") (pintype "input"))
    )
    (net (code "35") (name "Net-(U2-CELL1)") (class "Default")
      (node (ref "C13") (pin "2") (pinfunction "2_2") (pintype "passive"))
      (node (ref "C15") (pin "1") (pinfunction "1_1") (pintype "passive"))
      (node (ref "R55") (pin "2") (pinfunction "2_2") (pintype "passive"))
      (node (ref "TP25") (pin "1") (pinfunction "1_1") (pintype "passive"))
      (node (ref "U2") (pin "6") (pinfunction "CELL2_6") (pintype "passive"))
      (node (ref "U2") (pin "7") (pinfunction "CELL1_7") (pintype "passive"))
    )
    (net (code "36") (name "Net-(U2-REG2)") (class "Default")
      (node (ref "C9") (pin "1") (pinfunction "1_1") (pintype "passive"))
      (node (ref "U2") (pin "3") (pinfunction "REG2_3") (pintype "power_in"))
    )
    (net (code "37") (name "Net-(U2-REG3)") (class "Default")
      (node (ref "C3") (pin "1") (pinfunction "1_1") (pintype "passive"))
      (node (ref "U2") (pin "1") (pinfunction "REG3_1") (pintype "power_in"))
    )
    (net (code "38") (name "Net-(U2-THRM)") (class "Default")
      (node (ref "R41") (pin "2") (pinfunction "2_2") (pintype "passive"))
      (node (ref "R42") (pin "2") (pinfunction "2_2") (pintype "passive"))
      (node (ref "U2") (pin "14") (pinfunction "THRM_14") (pintype "passive"))
    )
    (net (code "39") (name "Net-(U2-VBATT)") (class "Default")
      (node (ref "C13") (pin "1") (pinfunction "1_1") (pintype "passive"))
      (node (ref "C14") (pin "1") (pinfunction "1_1") (pintype "passive"))
      (node (ref "R39") (pin "1") (pinfunction "1_1") (pintype "passive"))
      (node (ref "U2") (pin "5") (pinfunction "VBATT_5") (pintype "power_in"))
    )
    (net (code "40") (name "Net-(U10-SENSE)") (class "Default")
      (node (ref "Q14") (pin "1") (pinfunction "S_1") (pintype "passive"))
      (node (ref "Q14") (pin "2") (pinfunction "S_2") (pintype "passive"))
      (node (ref "Q14") (pin "3") (pinfunction "S_3") (pintype "passive"))
      (node (ref "Q16") (pin "5") (pinfunction "D_5") (pintype "passive"))
      (node (ref "Q16") (pin "6") (pinfunction "D_6") (pintype "passive"))
      (node (ref "Q16") (pin "7") (pinfunction "D_7") (pintype "passive"))
      (node (ref "Q16") (pin "8") (pinfunction "D_8") (pintype "passive"))
      (node (ref "Q16") (pin "PAD") (pinfunction "D_PAD") (pintype "passive"))
      (node (ref "R50") (pin "2") (pinfunction "2_2") (pintype "passive"))
      (node (ref "R70") (pin "1") (pinfunction "1_1") (pintype "passive"))
      (node (ref "R73") (pin "1") (pinfunction "1_1") (pintype "passive"))
      (node (ref "U10") (pin "6") (pinfunction "SENSE_6") (pintype "input"))
    )
    (net (code "41") (name "Net-(U11-CDT)") (class "Default")
      (node (ref "C18") (pin "1") (pinfunction "1_1") (pintype "passive"))
      (node (ref "U11") (pin "4") (pinfunction "CDT_4") (pintype "passive"))
    )
    (net (code "42") (name "Net-(U11-CTLC)") (class "Default")
      (node (ref "R48") (pin "2") (pinfunction "2_2") (pintype "passive"))
      (node (ref "TP23") (pin "1") (pinfunction "1_1") (pintype "passive"))
      (node (ref "U11") (pin "1") (pinfunction "CTLC_1") (pintype "passive"))
    )
    (net (code "43") (name "Net-(U11-CTLD)") (class "Default")
      (node (ref "R47") (pin "2") (pinfunction "2_2") (pintype "passive"))
      (node (ref "TP24") (pin "1") (pinfunction "1_1") (pintype "passive"))
      (node (ref "U11") (pin "2") (pinfunction "CTLD_2") (pintype "input"))
    )
    (net (code "44") (name "Net-(U11-VDD)") (class "Default")
      (node (ref "R53") (pin "1") (pinfunction "1_1") (pintype "passive"))
      (node (ref "U11") (pin "3") (pinfunction "VDD_3") (pintype "power_in"))
    )
    (net (code "45") (name "Net-(U11-VSS)") (class "Default")
      (node (ref "C18") (pin "2") (pinfunction "2_2") (pintype "passive"))
      (node (ref "C19") (pin "1") (pinfunction "1_1") (pintype "passive"))
      (node (ref "C21") (pin "2") (pinfunction "2_2") (pintype "passive"))
      (node (ref "JP6") (pin "2") (pinfunction "2_2") (pintype "passive"))
      (node (ref "Q2") (pin "5") (pinfunction "D_5") (pintype "passive"))
      (node (ref "Q2") (pin "6") (pinfunction "D_6") (pintype "passive"))
      (node (ref "Q2") (pin "7") (pinfunction "D_7") (pintype "passive"))
      (node (ref "Q2") (pin "8") (pinfunction "D_8") (pintype "passive"))
      (node (ref "Q2") (pin "PAD") (pinfunction "D_PAD") (pintype "passive"))
      (node (ref "R54") (pin "2") (pinfunction "2_2") (pintype "passive"))
      (node (ref "R55") (pin "1") (pinfunction "1_1") (pintype "passive"))
      (node (ref "R67") (pin "1") (pinfunction "1_1") (pintype "passive"))
      (node (ref "R69") (pin "2") (pinfunction "2_2") (pintype "passive"))
      (node (ref "R7") (pin "2") (pinfunction "2_2") (pintype "passive"))
      (node (ref "TP5") (pin "1") (pinfunction "1_1") (pintype "passive"))
      (node (ref "U11") (pin "5") (pinfunction "VSS_5") (pintype "power_in"))
    )
    (net (code "46") (name "Net-(U12-CDT)") (class "Default")
      (node (ref "C20") (pin "1") (pinfunction "1_1") (pintype "passive"))
      (node (ref "U12") (pin "4") (pinfunction "CDT_4") (pintype "passive"))
    )
    (net (code "47") (name "Net-(U12-CO)") (class "Default")
      (node (ref "R48") (pin "1") (pinfunction "1_1") (pintype "passive"))
      (node (ref "U12") (pin "7") (pinfunction "CO_7") (pintype "open_collector"))
    )
    (net (code "48") (name "Net-(U12-CTLC)") (class "Default")
      (node (ref "R6") (pin "2") (pinfunction "2_2") (pintype "passive"))
      (node (ref "TP22") (pin "1") (pinfunction "1_1") (pintype "passive"))
      (node (ref "U12") (pin "1") (pinfunction "CTLC_1") (pintype "passive"))
    )
    (net (code "49") (name "Net-(U12-CTLD)") (class "Default")
      (node (ref "R66") (pin "2") (pinfunction "2_2") (pintype "passive"))
      (node (ref "TP21") (pin "1") (pinfunction "1_1") (pintype "passive"))
      (node (ref "U12") (pin "2") (pinfunction "CTLD_2") (pintype "input"))
    )
    (net (code "50") (name "Net-(U12-DO)") (class "Default")
      (node (ref "R47") (pin "1") (pinfunction "1_1") (pintype "passive"))
      (node (ref "U12") (pin "6") (pinfunction "DO_6") (pintype "open_collector"))
    )
    (net (code "51") (name "Net-(U12-VDD)") (class "Default")
      (node (ref "R54") (pin "1") (pinfunction "1_1") (pintype "passive"))
      (node (ref "U12") (pin "3") (pinfunction "VDD_3") (pintype "power_in"))
    )
    (net (code "52") (name "VBUS") (class "Default")
      (node (ref "C31") (pin "1") (pinfunction "1_1") (pintype "passive"))
      (node (ref "JP8") (pin "1") (pinfunction "1_1") (pintype "passive"))
      (node (ref "JP8") (pin "2") (pinfunction "2_2") (pintype "passive"))
      (node (ref "Q12") (pin "5") (pinfunction "D_5") (pintype "passive"))
      (node (ref "Q12") (pin "6") (pinfunction "D_6") (pintype "passive"))
      (node (ref "Q12") (pin "7") (pinfunction "D_7") (pintype "passive"))
      (node (ref "Q12") (pin "8") (pinfunction "D_8") (pintype "passive"))
      (node (ref "Q12") (pin "PAD") (pinfunction "D_PAD") (pintype "passive"))
      (node (ref "Q15") (pin "5") (pinfunction "D_5") (pintype "passive"))
      (node (ref "Q15") (pin "6") (pinfunction "D_6") (pintype "passive"))
      (node (ref "Q15") (pin "7") (pinfunction "D_7") (pintype "passive"))
      (node (ref "Q15") (pin "8") (pinfunction "D_8") (pintype "passive"))
      (node (ref "Q15") (pin "PAD") (pinfunction "D_PAD") (pintype "passive"))
      (node (ref "U10") (pin "1") (pinfunction "VIN_1") (pintype "power_in"))
      (node (ref "U9") (pin "6") (pinfunction "SENSE_6") (pintype "input"))
    )
    (net (code "53") (name "unconnected-(U2-CELLX-Pad13)") (class "Default")
      (node (ref "U2") (pin "13") (pinfunction "CELLX_13") (pintype "passive"))
    )
    (net (code "54") (name "unconnected-(U11-CB-Pad8)") (class "Default")
      (node (ref "U11") (pin "8") (pinfunction "CB_8") (pintype "output"))
    )
    (net (code "55") (name "unconnected-(U12-CB-Pad8)") (class "Default")
      (node (ref "U12") (pin "8") (pinfunction "CB_8") (pintype "output"))
    )
  )
)
